# Instrument_Cluster_2.net
KiCad netlist of a schematic drawn in EAGLE
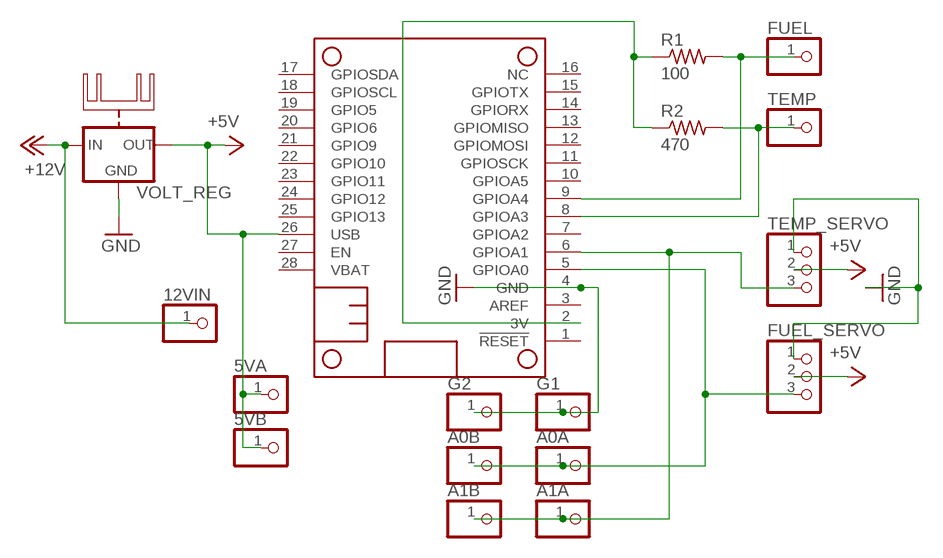
[diagram p0: schematic, sheet 1]

(export (version "E")
  (design (tool "Eeschema 10.0.6"))
  (components
    (comp (ref "5VA")
      (value "PINHD-1X1")
      (footprint "eagle-import:1X01")
      (libsource (lib "eagle-import") (part "PINHD-1X1"))
    )
    (comp (ref "5VB")
      (value "PINHD-1X1")
      (footprint "eagle-import:1X01")
      (libsource (lib "eagle-import") (part "PINHD-1X1"))
    )
    (comp (ref "12VIN")
      (value "PINHD-1X1")
      (footprint "eagle-import:1X01")
      (libsource (lib "eagle-import") (part "PINHD-1X1"))
    )
    (comp (ref "A0A")
      (value "PINHD-1X1")
      (footprint "eagle-import:1X01")
      (libsource (lib "eagle-import") (part "PINHD-1X1"))
    )
    (comp (ref "A0B")
      (value "PINHD-1X1")
      (footprint "eagle-import:1X01")
      (libsource (lib "eagle-import") (part "PINHD-1X1"))
    )
    (comp (ref "A1A")
      (value "PINHD-1X1")
      (footprint "eagle-import:1X01")
      (libsource (lib "eagle-import") (part "PINHD-1X1"))
    )
    (comp (ref "A1B")
      (value "PINHD-1X1")
      (footprint "eagle-import:1X01")
      (libsource (lib "eagle-import") (part "PINHD-1X1"))
    )
    (comp (ref "FUEL")
      (value "PINHD-1X1")
      (footprint "eagle-import:1X01")
      (libsource (lib "eagle-import") (part "PINHD-1X1"))
    )
    (comp (ref "FUEL_SERVO")
      (value "PINHD-1X3")
      (footprint "eagle-import:1X03")
      (libsource (lib "eagle-import") (part "PINHD-1X3"))
    )
    (comp (ref "G1")
      (value "PINHD-1X1")
      (footprint "eagle-import:1X01")
      (libsource (lib "eagle-import") (part "PINHD-1X1"))
    )
    (comp (ref "G2")
      (value "PINHD-1X1")
      (footprint "eagle-import:1X01")
      (libsource (lib "eagle-import") (part "PINHD-1X1"))
    )
    (comp (ref "MS2")
      (value "FEATHERWING_NODIM")
      (footprint "eagle-import:FEATHERWING_DIM")
      (libsource (lib "eagle-import") (part "FEATHERWING_NODIM"))
    )
    (comp (ref "R1")
      (value "100")
      (footprint "eagle-import:0309_12")
      (libsource (lib "eagle-import") (part "R-US_0309/12"))
    )
    (comp (ref "R2")
      (value "470")
      (footprint "eagle-import:0309_12")
      (libsource (lib "eagle-import") (part "R-US_0309/12"))
    )
    (comp (ref "TEMP")
      (value "PINHD-1X1")
      (footprint "eagle-import:1X01")
      (libsource (lib "eagle-import") (part "PINHD-1X1"))
    )
    (comp (ref "TEMP_SERVO")
      (value "PINHD-1X3")
      (footprint "eagle-import:1X03")
      (libsource (lib "eagle-import") (part "PINHD-1X3"))
    )
    (comp (ref "VOLT_REG")
      (value "78XXH")
      (footprint "eagle-import:78XXH")
      (libsource (lib "eagle-import") (part "78XXH"))
    )
  )
  (nets
    (net (code "1") (name "+5V") (class "Default")
      (node (ref "5VA") (pin "1") (pinfunction "1_1") (pintype "passive"))
      (node (ref "5VB") (pin "1") (pinfunction "1_1") (pintype "passive"))
      (node (ref "FUEL_SERVO") (pin "2") (pinfunction "2_2") (pintype "passive"))
      (node (ref "MS2") (pin "26") (pinfunction "USB_26") (pintype "power_in"))
      (node (ref "TEMP_SERVO") (pin "2") (pinfunction "2_2") (pintype "passive"))
      (node (ref "VOLT_REG") (pin "OUT") (pinfunction "OUT_OUT") (pintype "passive"))
    )
    (net (code "2") (name "+12V") (class "Default")
      (node (ref "12VIN") (pin "1") (pinfunction "1_1") (pintype "passive"))
      (node (ref "VOLT_REG") (pin "IN") (pinfunction "IN_IN") (pintype "input"))
    )
    (net (code "3") (name "/VBAT") (class "Default")
      (node (ref "MS2") (pin "28") (pinfunction "VBAT_28") (pintype "power_in"))
    )
    (net (code "4") (name "GND") (class "Default")
      (node (ref "FUEL_SERVO") (pin "1") (pinfunction "1_1") (pintype "passive"))
      (node (ref "G1") (pin "1") (pinfunction "1_1") (pintype "passive"))
      (node (ref "G2") (pin "1") (pinfunction "1_1") (pintype "passive"))
      (node (ref "MS2") (pin "4") (pinfunction "GND_4") (pintype "power_in"))
      (node (ref "TEMP_SERVO") (pin "1") (pinfunction "1_1") (pintype "passive"))
      (node (ref "VOLT_REG") (pin "GND") (pinfunction "GND_GND") (pintype "input"))
    )
    (net (code "5") (name "Net-(MS2-3V)") (class "Default")
      (node (ref "MS2") (pin "2") (pinfunction "3V_2") (pintype "power_in"))
      (node (ref "R1") (pin "1") (pinfunction "1_1") (pintype "passive"))
      (node (ref "R2") (pin "1") (pinfunction "1_1") (pintype "passive"))
    )
    (net (code "6") (name "Net-(MS2-GPIOA0)") (class "Default")
      (node (ref "A0A") (pin "1") (pinfunction "1_1") (pintype "passive"))
      (node (ref "A0B") (pin "1") (pinfunction "1_1") (pintype "passive"))
      (node (ref "FUEL_SERVO") (pin "3") (pinfunction "3_3") (pintype "passive"))
      (node (ref "MS2") (pin "5") (pinfunction "GPIOA0_5") (pintype "bidirectional"))
    )
    (net (code "7") (name "Net-(MS2-GPIOA1)") (class "Default")
      (node (ref "A1A") (pin "1") (pinfunction "1_1") (pintype "passive"))
      (node (ref "A1B") (pin "1") (pinfunction "1_1") (pintype "passive"))
      (node (ref "MS2") (pin "6") (pinfunction "GPIOA1_6") (pintype "bidirectional"))
      (node (ref "TEMP_SERVO") (pin "3") (pinfunction "3_3") (pintype "passive"))
    )
    (net (code "8") (name "Net-(MS2-GPIOA3)") (class "Default")
      (node (ref "MS2") (pin "8") (pinfunction "GPIOA3_8") (pintype "bidirectional"))
      (node (ref "R2") (pin "2") (pinfunction "2_2") (pintype "passive"))
      (node (ref "TEMP") (pin "1") (pinfunction "1_1") (pintype "passive"))
    )
    (net (code "9") (name "Net-(MS2-GPIOA4)") (class "Default")
      (node (ref "FUEL") (pin "1") (pinfunction "1_1") (pintype "passive"))
      (node (ref "MS2") (pin "9") (pinfunction "GPIOA4_9") (pintype "bidirectional"))
      (node (ref "R1") (pin "2") (pinfunction "2_2") (pintype "passive"))
    )
    (net (code "10") (name "unconnected-(MS2-AREF-Pad3)") (class "Default")
      (node (ref "MS2") (pin "3") (pinfunction "AREF_3") (pintype "passive"))
    )
    (net (code "11") (name "unconnected-(MS2-EN-Pad27)") (class "Default")
      (node (ref "MS2") (pin "27") (pinfunction "EN_27") (pintype "passive"))
    )
    (net (code "12") (name "unconnected-(MS2-GPIO5-Pad19)") (class "Default")
      (node (ref "MS2") (pin "19") (pinfunction "GPIO5_19") (pintype "bidirectional"))
    )
    (net (code "13") (name "unconnected-(MS2-GPIO6-Pad20)") (class "Default")
      (node (ref "MS2") (pin "20") (pinfunction "GPIO6_20") (pintype "bidirectional"))
    )
    (net (code "14") (name "unconnected-(MS2-GPIO9-Pad21)") (class "Default")
      (node (ref "MS2") (pin "21") (pinfunction "GPIO9_21") (pintype "bidirectional"))
    )
    (net (code "15") (name "unconnected-(MS2-GPIO10-Pad22)") (class "Default")
      (node (ref "MS2") (pin "22") (pinfunction "GPIO10_22") (pintype "bidirectional"))
    )
    (net (code "16") (name "unconnected-(MS2-GPIO11-Pad23)") (class "Default")
      (node (ref "MS2") (pin "23") (pinfunction "GPIO11_23") (pintype "bidirectional"))
    )
    (net (code "17") (name "unconnected-(MS2-GPIO12-Pad24)") (class "Default")
      (node (ref "MS2") (pin "24") (pinfunction "GPIO12_24") (pintype "bidirectional"))
    )
    (net (code "18") (name "unconnected-(MS2-GPIO13-Pad25)") (class "Default")
      (node (ref "MS2") (pin "25") (pinfunction "GPIO13_25") (pintype "bidirectional"))
    )
    (net (code "19") (name "unconnected-(MS2-GPIOA2-Pad7)") (class "Default")
      (node (ref "MS2") (pin "7") (pinfunction "GPIOA2_7") (pintype "bidirectional"))
    )
    (net (code "20") (name "unconnected-(MS2-GPIOA5-Pad10)") (class "Default")
      (node (ref "MS2") (pin "10") (pinfunction "GPIOA5_10") (pintype "bidirectional"))
    )
    (net (code "21") (name "unconnected-(MS2-GPIOMISO-Pad13)") (class "Default")
      (node (ref "MS2") (pin "13") (pinfunction "GPIOMISO_13") (pintype "bidirectional"))
    )
    (net (code "22") (name "unconnected-(MS2-GPIOMOSI-Pad12)") (class "Default")
      (node (ref "MS2") (pin "12") (pinfunction "GPIOMOSI_12") (pintype "bidirectional"))
    )
    (net (code "23") (name "unconnected-(MS2-GPIORX-Pad14)") (class "Default")
      (node (ref "MS2") (pin "14") (pinfunction "GPIORX_14") (pintype "bidirectional"))
    )
    (net (code "24") (name "unconnected-(MS2-GPIOSCK-Pad11)") (class "Default")
      (node (ref "MS2") (pin "11") (pinfunction "GPIOSCK_11") (pintype "bidirectional"))
    )
    (net (code "25") (name "unconnected-(MS2-GPIOSCL-Pad18)") (class "Default")
      (node (ref "MS2") (pin "18") (pinfunction "GPIOSCL_18") (pintype "bidirectional"))
    )
    (net (code "26") (name "unconnected-(MS2-GPIOSDA-Pad17)") (class "Default")
      (node (ref "MS2") (pin "17") (pinfunction "GPIOSDA_17") (pintype "bidirectional"))
    )
    (net (code "27") (name "unconnected-(MS2-GPIOTX-Pad15)") (class "Default")
      (node (ref "MS2") (pin "15") (pinfunction "GPIOTX_15") (pintype "bidirectional"))
    )
    (net (code "28") (name "unconnected-(MS2-NC-Pad16)") (class "Default")
      (node (ref "MS2") (pin "16") (pinfunction "NC_16") (pintype "passive"))
    )
    (net (code "29") (name "unconnected-(MS2-~{RESET}-Pad1)") (class "Default")
      (node (ref "MS2") (pin "1") (pinfunction "~{RESET}_1") (pintype "input"))
    )
  )
)
